# proj_arhipov_buck.net
KiCad netlist of a schematic drawn in Altium Designer
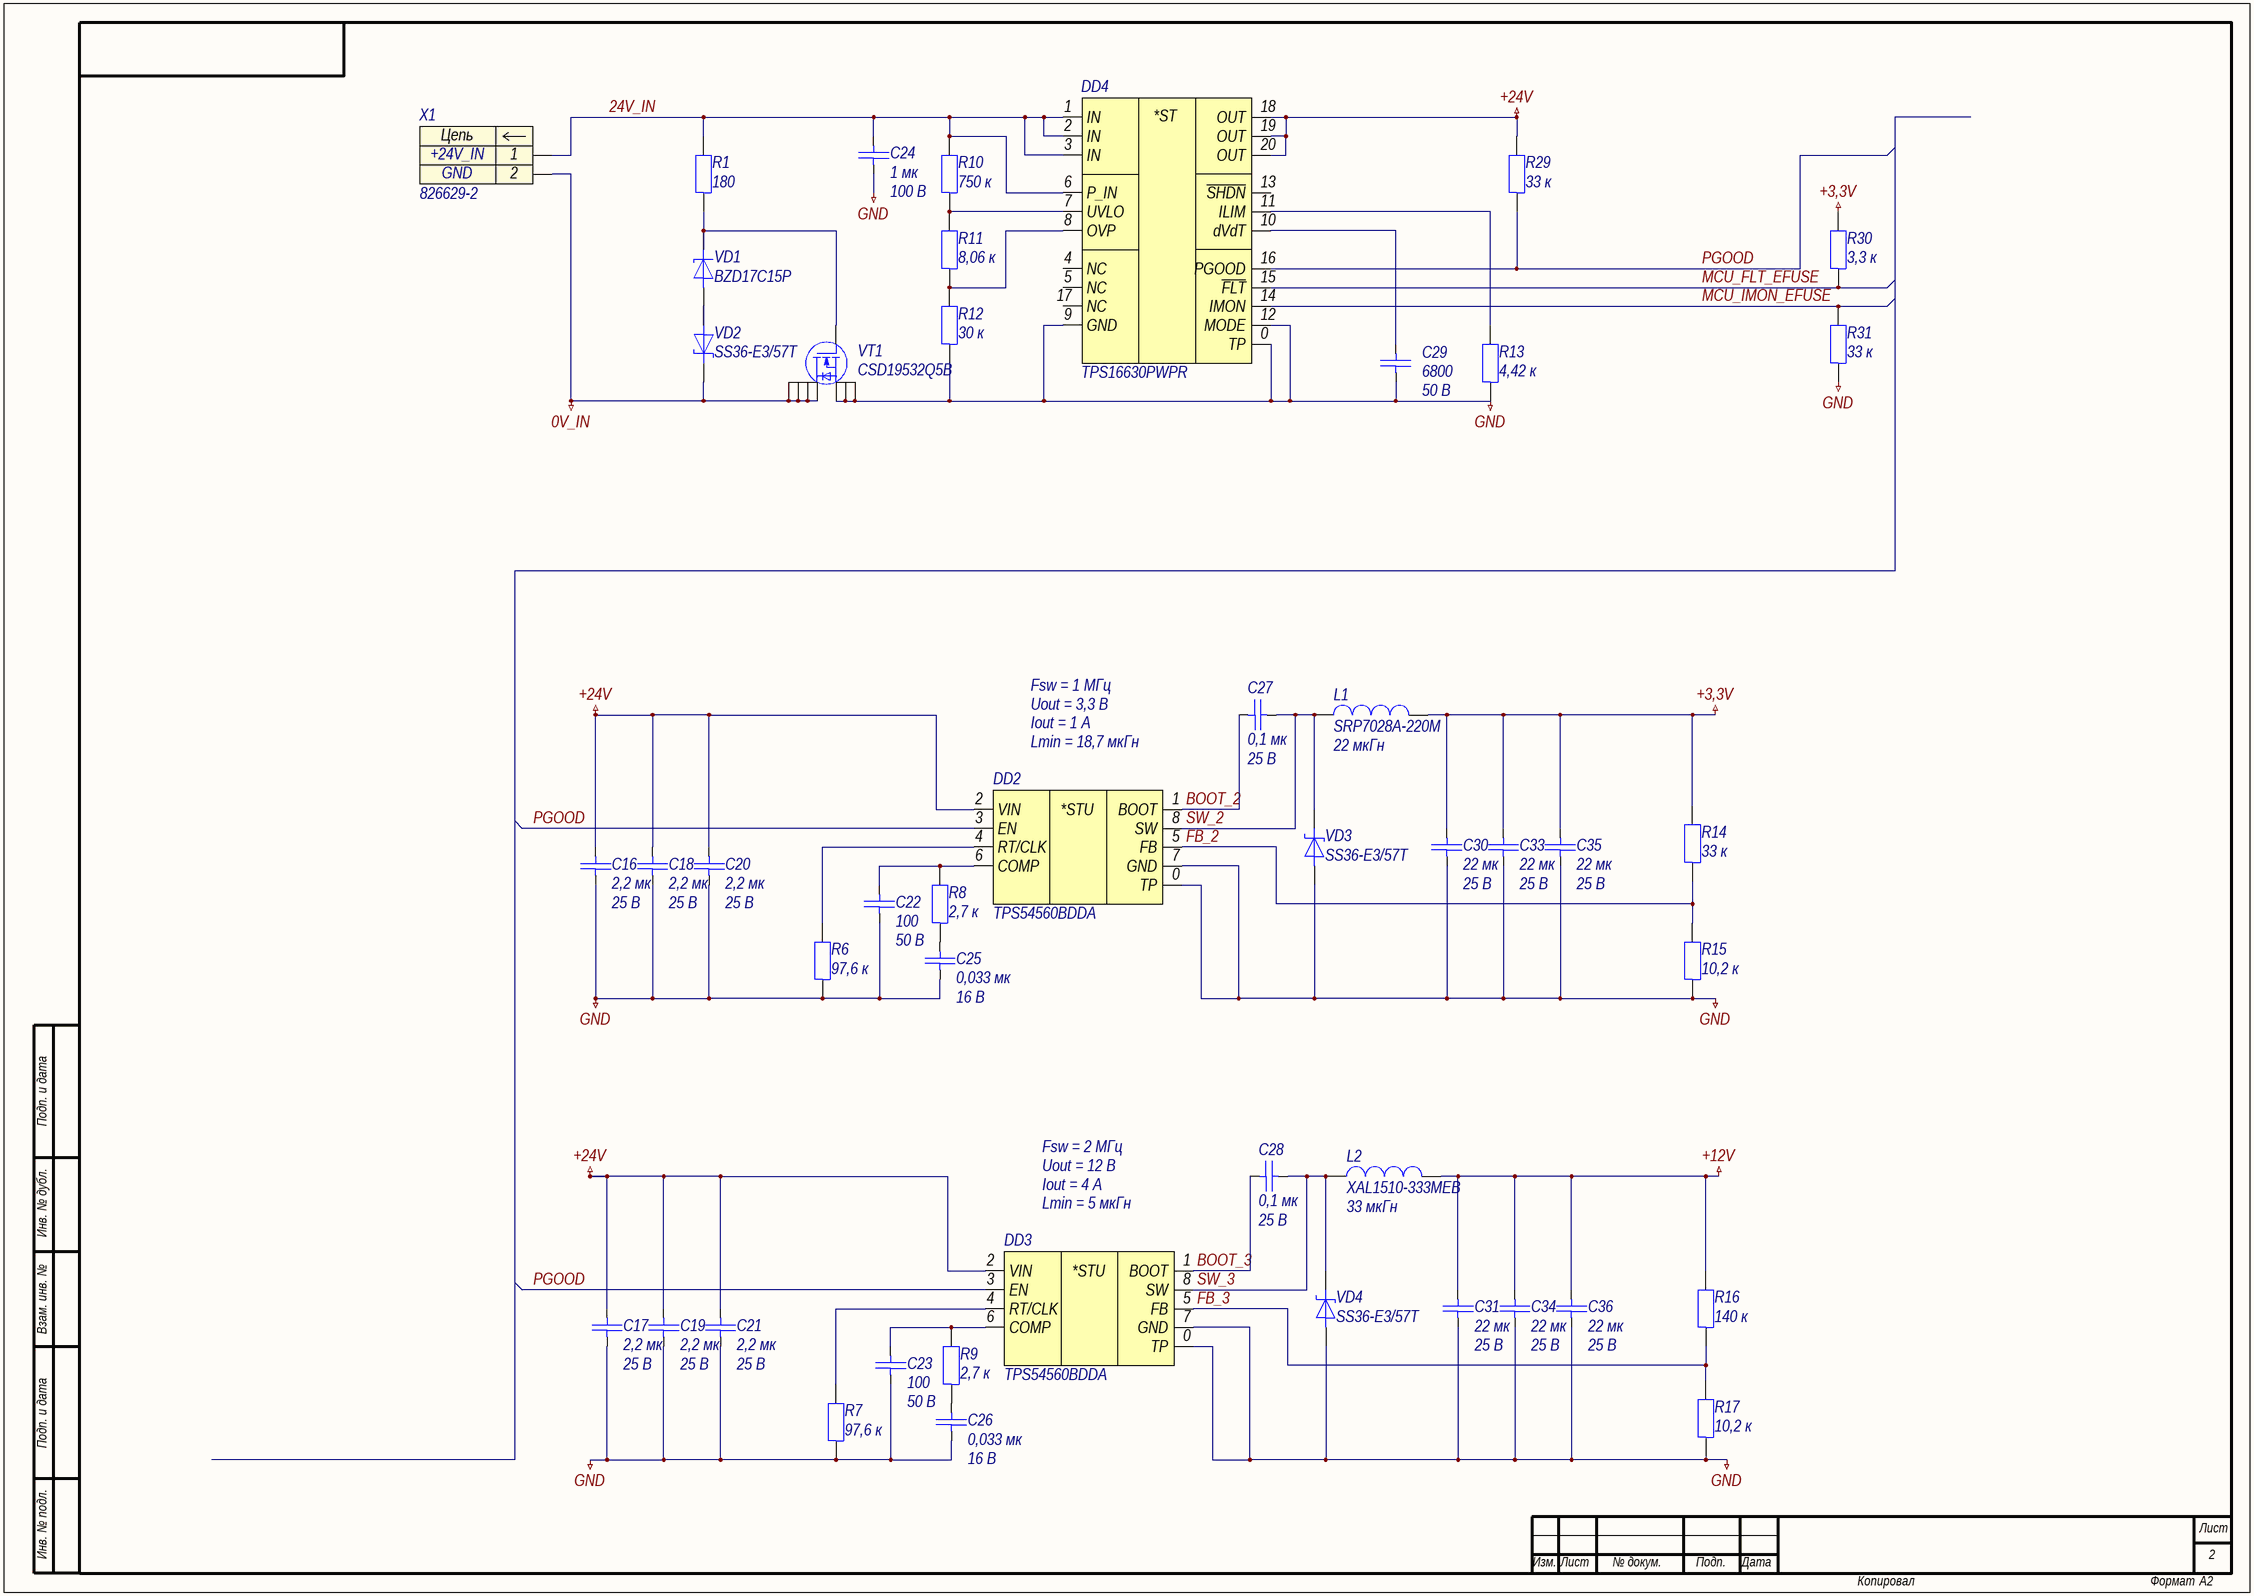
[diagram p0: proj_arhipov_buck.SchDoc]

(export (version "E")
  (design (tool "Eeschema 10.0.6"))
  (components
    (comp (ref "C16")
      (value "2,2 мк")
      (footprint "C0603")
      (description "=Описание")
      (fields (field (name "НАПРЯЖЕНИЕ") "25 В"))
      (libsource (lib "Database_Students") (part "CAPACITOR-NONPOLAR"))
    )
    (comp (ref "C17")
      (value "2,2 мк")
      (footprint "C0603")
      (description "=Описание")
      (fields (field (name "НАПРЯЖЕНИЕ") "25 В"))
      (libsource (lib "Database_Students") (part "CAPACITOR-NONPOLAR"))
    )
    (comp (ref "C18")
      (value "2,2 мк")
      (footprint "C0603")
      (description "=Описание")
      (fields (field (name "НАПРЯЖЕНИЕ") "25 В"))
      (libsource (lib "Database_Students") (part "CAPACITOR-NONPOLAR"))
    )
    (comp (ref "C19")
      (value "2,2 мк")
      (footprint "C0603")
      (description "=Описание")
      (fields (field (name "НАПРЯЖЕНИЕ") "25 В"))
      (libsource (lib "Database_Students") (part "CAPACITOR-NONPOLAR"))
    )
    (comp (ref "C20")
      (value "2,2 мк")
      (footprint "C0603")
      (description "=Описание")
      (fields (field (name "НАПРЯЖЕНИЕ") "25 В"))
      (libsource (lib "Database_Students") (part "CAPACITOR-NONPOLAR"))
    )
    (comp (ref "C21")
      (value "2,2 мк")
      (footprint "C0603")
      (description "=Описание")
      (fields (field (name "НАПРЯЖЕНИЕ") "25 В"))
      (libsource (lib "Database_Students") (part "CAPACITOR-NONPOLAR"))
    )
    (comp (ref "C22")
      (value "100")
      (footprint "C0402")
      (description "=Описание")
      (fields (field (name "НАПРЯЖЕНИЕ") "50 В"))
      (libsource (lib "Database_Students") (part "CAPACITOR-NONPOLAR"))
    )
    (comp (ref "C23")
      (value "100")
      (footprint "C0402")
      (description "=Описание")
      (fields (field (name "НАПРЯЖЕНИЕ") "50 В"))
      (libsource (lib "Database_Students") (part "CAPACITOR-NONPOLAR"))
    )
    (comp (ref "C24")
      (value "1 мк")
      (footprint "C1206")
      (description "=Описание")
      (fields (field (name "НАПРЯЖЕНИЕ") "100 В"))
      (libsource (lib "Database_Students") (part "CAPACITOR-NONPOLAR"))
    )
    (comp (ref "C25")
      (value "0,033 мк")
      (footprint "C0603")
      (description "=Описание")
      (fields (field (name "НАПРЯЖЕНИЕ") "16 В"))
      (libsource (lib "Database_Students") (part "CAPACITOR-NONPOLAR"))
    )
    (comp (ref "C26")
      (value "0,033 мк")
      (footprint "C0603")
      (description "=Описание")
      (fields (field (name "НАПРЯЖЕНИЕ") "16 В"))
      (libsource (lib "Database_Students") (part "CAPACITOR-NONPOLAR"))
    )
    (comp (ref "C27")
      (value "0,1 мк")
      (footprint "C0603")
      (description "=Описание")
      (fields (field (name "НАПРЯЖЕНИЕ") "25 В"))
      (libsource (lib "Database_Students") (part "CAPACITOR-NONPOLAR"))
    )
    (comp (ref "C28")
      (value "0,1 мк")
      (footprint "C0603")
      (description "=Описание")
      (fields (field (name "НАПРЯЖЕНИЕ") "25 В"))
      (libsource (lib "Database_Students") (part "CAPACITOR-NONPOLAR"))
    )
    (comp (ref "C29")
      (value "6800")
      (footprint "C0402")
      (description "=Описание")
      (fields (field (name "НАПРЯЖЕНИЕ") "50 В"))
      (libsource (lib "Database_Students") (part "CAPACITOR-NONPOLAR"))
    )
    (comp (ref "C30")
      (value "22 мк")
      (footprint "C1206")
      (description "=Описание")
      (fields (field (name "НАПРЯЖЕНИЕ") "25 В"))
      (libsource (lib "Database_Students") (part "CAPACITOR-NONPOLAR"))
    )
    (comp (ref "C31")
      (value "22 мк")
      (footprint "C1206")
      (description "=Описание")
      (fields (field (name "НАПРЯЖЕНИЕ") "25 В"))
      (libsource (lib "Database_Students") (part "CAPACITOR-NONPOLAR"))
    )
    (comp (ref "C33")
      (value "22 мк")
      (footprint "C1206")
      (description "=Описание")
      (fields (field (name "НАПРЯЖЕНИЕ") "25 В"))
      (libsource (lib "Database_Students") (part "CAPACITOR-NONPOLAR"))
    )
    (comp (ref "C34")
      (value "22 мк")
      (footprint "C1206")
      (description "=Описание")
      (fields (field (name "НАПРЯЖЕНИЕ") "25 В"))
      (libsource (lib "Database_Students") (part "CAPACITOR-NONPOLAR"))
    )
    (comp (ref "C35")
      (value "22 мк")
      (footprint "C1206")
      (description "=Описание")
      (fields (field (name "НАПРЯЖЕНИЕ") "25 В"))
      (libsource (lib "Database_Students") (part "CAPACITOR-NONPOLAR"))
    )
    (comp (ref "C36")
      (value "22 мк")
      (footprint "C1206")
      (description "=Описание")
      (fields (field (name "НАПРЯЖЕНИЕ") "25 В"))
      (libsource (lib "Database_Students") (part "CAPACITOR-NONPOLAR"))
    )
    (comp (ref "DD2")
      (value "TPS54560BDDA")
      (footprint "HSOIC-8")
      (description "=Описание")
      (libsource (lib "Database_Students") (part "TPS54560BDDA"))
    )
    (comp (ref "DD3")
      (value "TPS54560BDDA")
      (footprint "HSOIC-8")
      (description "=Описание")
      (libsource (lib "Database_Students") (part "TPS54560BDDA"))
    )
    (comp (ref "DD4")
      (value "TPS16630PWPR")
      (footprint "HTSSOP-20")
      (description "=Описание")
      (libsource (lib "Database_Students") (part "TPS16630PWPR"))
    )
    (comp (ref "L1")
      (value "SRP7028A-220M")
      (footprint "SRP-2-730X660X280")
      (description "=Описание")
      (fields (field (name "ИНДУКТИВНОСТЬ") "22 мкГн"))
      (libsource (lib "Database_Students") (part "INDUCTOR-COMMON"))
    )
    (comp (ref "L2")
      (value "XAL1510-333MEB")
      (footprint "XAL-2-1620X1520X1100")
      (description "=Описание")
      (fields (field (name "ИНДУКТИВНОСТЬ") "33 мкГн"))
      (libsource (lib "Database_Students") (part "INDUCTOR-COMMON"))
    )
    (comp (ref "R1")
      (value "180")
      (footprint "R0603")
      (description "=Описание")
      (libsource (lib "Database_Students") (part "RESISTOR-COMMON"))
    )
    (comp (ref "R6")
      (value "97,6 к")
      (footprint "R0603")
      (description "=Описание")
      (libsource (lib "Database_Students") (part "R-COMMON"))
    )
    (comp (ref "R7")
      (value "97,6 к")
      (footprint "R0603")
      (description "=Описание")
      (libsource (lib "Database_Students") (part "R-COMMON"))
    )
    (comp (ref "R8")
      (value "2,7 к")
      (footprint "R0603")
      (description "=Описание")
      (libsource (lib "Database_Students") (part "RESISTOR-COMMON"))
    )
    (comp (ref "R9")
      (value "2,7 к")
      (footprint "R0603")
      (description "=Описание")
      (libsource (lib "Database_Students") (part "RESISTOR-COMMON"))
    )
    (comp (ref "R10")
      (value "750 к")
      (footprint "R0603")
      (description "=Описание")
      (libsource (lib "Database_Students") (part "RESISTOR-COMMON"))
    )
    (comp (ref "R11")
      (value "8,06 к")
      (footprint "R0603")
      (description "=Описание")
      (libsource (lib "Database_Students") (part "R-COMMON"))
    )
    (comp (ref "R12")
      (value "30 к")
      (footprint "R0603")
      (description "=Описание")
      (libsource (lib "Database_Students") (part "RESISTOR-COMMON"))
    )
    (comp (ref "R13")
      (value "4,42 к")
      (footprint "R0603")
      (description "=Описание")
      (libsource (lib "Database_Students") (part "RESISTOR-COMMON"))
    )
    (comp (ref "R14")
      (value "33 к")
      (footprint "R0603")
      (description "=Описание")
      (libsource (lib "Database_Students") (part "RESISTOR-COMMON"))
    )
    (comp (ref "R15")
      (value "10,2 к")
      (footprint "R0603")
      (description "=Описание")
      (libsource (lib "Database_Students") (part "R-COMMON"))
    )
    (comp (ref "R16")
      (value "140 к")
      (footprint "R0603")
      (description "=Описание")
      (libsource (lib "Database_Students") (part "RESISTOR-COMMON"))
    )
    (comp (ref "R17")
      (value "10,2 к")
      (footprint "R0603")
      (description "=Описание")
      (libsource (lib "Database_Students") (part "R-COMMON"))
    )
    (comp (ref "R29")
      (value "33 к")
      (footprint "R0603")
      (description "=Описание")
      (libsource (lib "Database_Students") (part "RESISTOR-COMMON"))
    )
    (comp (ref "R30")
      (value "3,3 к")
      (footprint "R0603")
      (description "=Описание")
      (libsource (lib "Database_Students") (part "RESISTOR-COMMON"))
    )
    (comp (ref "R31")
      (value "33 к")
      (footprint "R0603")
      (description "=Описание")
      (libsource (lib "Database_Students") (part "RESISTOR-COMMON"))
    )
    (comp (ref "VD1")
      (value "BZD17C15P")
      (footprint "DO-219AB")
      (description "=Описание")
      (libsource (lib "Database_Students") (part "ZENER-DIODE"))
    )
    (comp (ref "VD2")
      (value "SS36-E3/57T")
      (footprint "DO-214AB")
      (description "=Описание")
      (libsource (lib "Database_Students") (part "DIODE-SCHOTTKY"))
    )
    (comp (ref "VD3")
      (value "SS36-E3/57T")
      (footprint "DO-214AB")
      (description "=Описание")
      (libsource (lib "Database_Students") (part "DIODE-SCHOTTKY"))
    )
    (comp (ref "VD4")
      (value "SS36-E3/57T")
      (footprint "DO-214AB")
      (description "=Описание")
      (libsource (lib "Database_Students") (part "DIODE-SCHOTTKY"))
    )
    (comp (ref "VT1")
      (value "CSD19532Q5B")
      (footprint "SON-8-500X600X100")
      (description "=Описание")
      (libsource (lib "Database_Students") (part "MOSFET-N-3S-1G-4D"))
    )
    (comp (ref "X1")
      (value "826629-2")
      (footprint "SnapEDApcb:TE_826629-2")
      (fields (field (name "MF") "TE Connectivity"))
      (libsource (lib "SnapEDAsch") (part "826629-2"))
    )
  )
  (nets
    (net (code "1") (name "+3,3V") (class "Default")
      (node (ref "C30") (pin "1") (pinfunction "1_1") (pintype "passive"))
      (node (ref "C33") (pin "1") (pinfunction "1_1") (pintype "passive"))
      (node (ref "C35") (pin "1") (pinfunction "1_1") (pintype "passive"))
      (node (ref "L1") (pin "2") (pinfunction "2_2") (pintype "passive"))
      (node (ref "R14") (pin "2") (pinfunction "2_2") (pintype "passive"))
      (node (ref "R30") (pin "2") (pinfunction "2_2") (pintype "passive"))
    )
    (net (code "2") (name "+12V") (class "Default")
      (node (ref "C31") (pin "1") (pinfunction "1_1") (pintype "passive"))
      (node (ref "C34") (pin "1") (pinfunction "1_1") (pintype "passive"))
      (node (ref "C36") (pin "1") (pinfunction "1_1") (pintype "passive"))
      (node (ref "L2") (pin "2") (pinfunction "2_2") (pintype "passive"))
      (node (ref "R16") (pin "2") (pinfunction "2_2") (pintype "passive"))
    )
    (net (code "3") (name "+24V") (class "Default")
      (node (ref "C16") (pin "1") (pinfunction "1_1") (pintype "passive"))
      (node (ref "C17") (pin "1") (pinfunction "1_1") (pintype "passive"))
      (node (ref "C18") (pin "1") (pinfunction "1_1") (pintype "passive"))
      (node (ref "C19") (pin "1") (pinfunction "1_1") (pintype "passive"))
      (node (ref "C20") (pin "1") (pinfunction "1_1") (pintype "passive"))
      (node (ref "C21") (pin "1") (pinfunction "1_1") (pintype "passive"))
      (node (ref "DD2") (pin "2") (pinfunction "VIN_2") (pintype "passive"))
      (node (ref "DD3") (pin "2") (pinfunction "VIN_2") (pintype "passive"))
      (node (ref "DD4") (pin "18") (pinfunction "OUT_18") (pintype "passive"))
      (node (ref "DD4") (pin "19") (pinfunction "OUT_19") (pintype "passive"))
      (node (ref "DD4") (pin "20") (pinfunction "OUT_20") (pintype "passive"))
      (node (ref "R29") (pin "2") (pinfunction "2_2") (pintype "passive"))
    )
    (net (code "4") (name "/24V_IN") (class "Default")
      (node (ref "C24") (pin "1") (pinfunction "1_1") (pintype "passive"))
      (node (ref "DD4") (pin "1") (pinfunction "IN_1") (pintype "passive"))
      (node (ref "DD4") (pin "2") (pinfunction "IN_2") (pintype "passive"))
      (node (ref "DD4") (pin "3") (pinfunction "IN_3") (pintype "passive"))
      (node (ref "DD4") (pin "6") (pinfunction "P_IN_6") (pintype "passive"))
      (node (ref "R1") (pin "2") (pinfunction "2_2") (pintype "passive"))
      (node (ref "R10") (pin "2") (pinfunction "2_2") (pintype "passive"))
      (node (ref "X1") (pin "1") (pinfunction "1_1") (pintype "passive"))
    )
    (net (code "5") (name "/BOOT_2") (class "Default")
      (node (ref "C27") (pin "2") (pinfunction "2_2") (pintype "passive"))
      (node (ref "DD2") (pin "1") (pinfunction "BOOT_1") (pintype "passive"))
    )
    (net (code "6") (name "/BOOT_3") (class "Default")
      (node (ref "C28") (pin "2") (pinfunction "2_2") (pintype "passive"))
      (node (ref "DD3") (pin "1") (pinfunction "BOOT_1") (pintype "passive"))
    )
    (net (code "7") (name "/FB_2") (class "Default")
      (node (ref "DD2") (pin "5") (pinfunction "FB_5") (pintype "passive"))
      (node (ref "R14") (pin "1") (pinfunction "1_1") (pintype "passive"))
      (node (ref "R15") (pin "2") (pinfunction "2_2") (pintype "passive"))
    )
    (net (code "8") (name "/FB_3") (class "Default")
      (node (ref "DD3") (pin "5") (pinfunction "FB_5") (pintype "passive"))
      (node (ref "R16") (pin "1") (pinfunction "1_1") (pintype "passive"))
      (node (ref "R17") (pin "2") (pinfunction "2_2") (pintype "passive"))
    )
    (net (code "9") (name "/MCU_FLT_EFUSE") (class "Default")
      (node (ref "DD4") (pin "15") (pinfunction "~{FLT}_15") (pintype "passive"))
      (node (ref "R30") (pin "1") (pinfunction "1_1") (pintype "passive"))
    )
    (net (code "10") (name "/MCU_IMON_EFUSE") (class "Default")
      (node (ref "DD4") (pin "14") (pinfunction "IMON_14") (pintype "passive"))
      (node (ref "R31") (pin "2") (pinfunction "2_2") (pintype "passive"))
    )
    (net (code "11") (name "/PGOOD") (class "Default")
      (node (ref "DD2") (pin "3") (pinfunction "EN_3") (pintype "passive"))
      (node (ref "DD3") (pin "3") (pinfunction "EN_3") (pintype "passive"))
      (node (ref "DD4") (pin "16") (pinfunction "PGOOD_16") (pintype "passive"))
      (node (ref "R29") (pin "1") (pinfunction "1_1") (pintype "passive"))
    )
    (net (code "12") (name "/SW_2") (class "Default")
      (node (ref "C27") (pin "1") (pinfunction "1_1") (pintype "passive"))
      (node (ref "DD2") (pin "8") (pinfunction "SW_8") (pintype "passive"))
      (node (ref "L1") (pin "1") (pinfunction "1_1") (pintype "passive"))
      (node (ref "VD3") (pin "1") (pinfunction "1_1") (pintype "passive"))
    )
    (net (code "13") (name "/SW_3") (class "Default")
      (node (ref "C28") (pin "1") (pinfunction "1_1") (pintype "passive"))
      (node (ref "DD3") (pin "8") (pinfunction "SW_8") (pintype "passive"))
      (node (ref "L2") (pin "1") (pinfunction "1_1") (pintype "passive"))
      (node (ref "VD4") (pin "1") (pinfunction "1_1") (pintype "passive"))
    )
    (net (code "14") (name "0V_IN") (class "Default")
      (node (ref "VD2") (pin "1") (pinfunction "1_1") (pintype "passive"))
      (node (ref "VT1") (pin "5") (pinfunction "D_5") (pintype "passive"))
      (node (ref "VT1") (pin "6") (pinfunction "D_6") (pintype "passive"))
      (node (ref "VT1") (pin "7") (pinfunction "D_7") (pintype "passive"))
      (node (ref "VT1") (pin "8") (pinfunction "D_8") (pintype "passive"))
      (node (ref "X1") (pin "2") (pinfunction "2_2") (pintype "passive"))
    )
    (net (code "15") (name "GND") (class "Default")
      (node (ref "C16") (pin "2") (pinfunction "2_2") (pintype "passive"))
      (node (ref "C17") (pin "2") (pinfunction "2_2") (pintype "passive"))
      (node (ref "C18") (pin "2") (pinfunction "2_2") (pintype "passive"))
      (node (ref "C19") (pin "2") (pinfunction "2_2") (pintype "passive"))
      (node (ref "C20") (pin "2") (pinfunction "2_2") (pintype "passive"))
      (node (ref "C21") (pin "2") (pinfunction "2_2") (pintype "passive"))
      (node (ref "C22") (pin "2") (pinfunction "2_2") (pintype "passive"))
      (node (ref "C23") (pin "2") (pinfunction "2_2") (pintype "passive"))
      (node (ref "C24") (pin "2") (pinfunction "2_2") (pintype "passive"))
      (node (ref "C25") (pin "2") (pinfunction "2_2") (pintype "passive"))
      (node (ref "C26") (pin "2") (pinfunction "2_2") (pintype "passive"))
      (node (ref "C29") (pin "2") (pinfunction "2_2") (pintype "passive"))
      (node (ref "C30") (pin "2") (pinfunction "2_2") (pintype "passive"))
      (node (ref "C31") (pin "2") (pinfunction "2_2") (pintype "passive"))
      (node (ref "C33") (pin "2") (pinfunction "2_2") (pintype "passive"))
      (node (ref "C34") (pin "2") (pinfunction "2_2") (pintype "passive"))
      (node (ref "C35") (pin "2") (pinfunction "2_2") (pintype "passive"))
      (node (ref "C36") (pin "2") (pinfunction "2_2") (pintype "passive"))
      (node (ref "DD2") (pin "0") (pinfunction "TP_0") (pintype "passive"))
      (node (ref "DD2") (pin "7") (pinfunction "GND_7") (pintype "passive"))
      (node (ref "DD3") (pin "0") (pinfunction "TP_0") (pintype "passive"))
      (node (ref "DD3") (pin "7") (pinfunction "GND_7") (pintype "passive"))
      (node (ref "DD4") (pin "0") (pinfunction "TP_0") (pintype "passive"))
      (node (ref "DD4") (pin "12") (pinfunction "MODE_12") (pintype "passive"))
      (node (ref "DD4") (pin "9") (pinfunction "GND_9") (pintype "passive"))
      (node (ref "R12") (pin "1") (pinfunction "1_1") (pintype "passive"))
      (node (ref "R13") (pin "1") (pinfunction "1_1") (pintype "passive"))
      (node (ref "R15") (pin "1") (pinfunction "1_1") (pintype "passive"))
      (node (ref "R17") (pin "1") (pinfunction "1_1") (pintype "passive"))
      (node (ref "R31") (pin "1") (pinfunction "1_1") (pintype "passive"))
      (node (ref "R6") (pin "1") (pinfunction "1_1") (pintype "passive"))
      (node (ref "R7") (pin "1") (pinfunction "1_1") (pintype "passive"))
      (node (ref "VD3") (pin "2") (pinfunction "2_2") (pintype "passive"))
      (node (ref "VD4") (pin "2") (pinfunction "2_2") (pintype "passive"))
      (node (ref "VT1") (pin "1") (pinfunction "S_1") (pintype "passive"))
      (node (ref "VT1") (pin "2") (pinfunction "S_2") (pintype "passive"))
      (node (ref "VT1") (pin "3") (pintype "passive"))
    )
    (net (code "16") (name "Net-(C25-Pad1)") (class "Default")
      (node (ref "C25") (pin "1") (pinfunction "1_1") (pintype "passive"))
      (node (ref "R8") (pin "1") (pinfunction "1_1") (pintype "passive"))
    )
    (net (code "17") (name "Net-(C26-Pad1)") (class "Default")
      (node (ref "C26") (pin "1") (pinfunction "1_1") (pintype "passive"))
      (node (ref "R9") (pin "1") (pinfunction "1_1") (pintype "passive"))
    )
    (net (code "18") (name "Net-(DD2-COMP)") (class "Default")
      (node (ref "C22") (pin "1") (pinfunction "1_1") (pintype "passive"))
      (node (ref "DD2") (pin "6") (pinfunction "COMP_6") (pintype "passive"))
      (node (ref "R8") (pin "2") (pinfunction "2_2") (pintype "passive"))
    )
    (net (code "19") (name "Net-(DD2-RT{slash}CLK)") (class "Default")
      (node (ref "DD2") (pin "4") (pinfunction "RT/CLK_4") (pintype "passive"))
      (node (ref "R6") (pin "2") (pinfunction "2_2") (pintype "passive"))
    )
    (net (code "20") (name "Net-(DD3-COMP)") (class "Default")
      (node (ref "C23") (pin "1") (pinfunction "1_1") (pintype "passive"))
      (node (ref "DD3") (pin "6") (pinfunction "COMP_6") (pintype "passive"))
      (node (ref "R9") (pin "2") (pinfunction "2_2") (pintype "passive"))
    )
    (net (code "21") (name "Net-(DD3-RT{slash}CLK)") (class "Default")
      (node (ref "DD3") (pin "4") (pinfunction "RT/CLK_4") (pintype "passive"))
      (node (ref "R7") (pin "2") (pinfunction "2_2") (pintype "passive"))
    )
    (net (code "22") (name "Net-(DD4-ILIM)") (class "Default")
      (node (ref "DD4") (pin "11") (pinfunction "ILIM_11") (pintype "passive"))
      (node (ref "R13") (pin "2") (pinfunction "2_2") (pintype "passive"))
    )
    (net (code "23") (name "Net-(DD4-OVP)") (class "Default")
      (node (ref "DD4") (pin "8") (pinfunction "OVP_8") (pintype "passive"))
      (node (ref "R11") (pin "1") (pinfunction "1_1") (pintype "passive"))
      (node (ref "R12") (pin "2") (pinfunction "2_2") (pintype "passive"))
    )
    (net (code "24") (name "Net-(DD4-UVLO)") (class "Default")
      (node (ref "DD4") (pin "7") (pinfunction "UVLO_7") (pintype "passive"))
      (node (ref "R10") (pin "1") (pinfunction "1_1") (pintype "passive"))
      (node (ref "R11") (pin "2") (pinfunction "2_2") (pintype "passive"))
    )
    (net (code "25") (name "Net-(DD4-dVdT)") (class "Default")
      (node (ref "C29") (pin "1") (pinfunction "1_1") (pintype "passive"))
      (node (ref "DD4") (pin "10") (pinfunction "dVdT_10") (pintype "passive"))
    )
    (net (code "26") (name "Net-(VD1-Pad2)") (class "Default")
      (node (ref "VD1") (pin "2") (pinfunction "2_2") (pintype "passive"))
      (node (ref "VD2") (pin "2") (pinfunction "2_2") (pintype "passive"))
    )
    (net (code "27") (name "Net-(VT1-G)") (class "Default")
      (node (ref "R1") (pin "1") (pinfunction "1_1") (pintype "passive"))
      (node (ref "VD1") (pin "1") (pinfunction "1_1") (pintype "passive"))
      (node (ref "VT1") (pin "4") (pinfunction "G_4") (pintype "passive"))
    )
    (net (code "28") (name "unconnected-(DD4-NC-Pad4)") (class "Default")
      (node (ref "DD4") (pin "4") (pinfunction "NC_4") (pintype "passive"))
    )
    (net (code "29") (name "unconnected-(DD4-NC-Pad5)") (class "Default")
      (node (ref "DD4") (pin "5") (pinfunction "NC_5") (pintype "passive"))
    )
    (net (code "30") (name "unconnected-(DD4-NC-Pad17)") (class "Default")
      (node (ref "DD4") (pin "17") (pinfunction "NC_17") (pintype "passive"))
    )
    (net (code "31") (name "unconnected-(DD4-~{SHDN}-Pad13)") (class "Default")
      (node (ref "DD4") (pin "13") (pinfunction "~{SHDN}_13") (pintype "passive"))
    )
  )
)
